# ESP32-HWE-Dev-SPI.net
KiCad netlist of a schematic drawn in Altium Designer
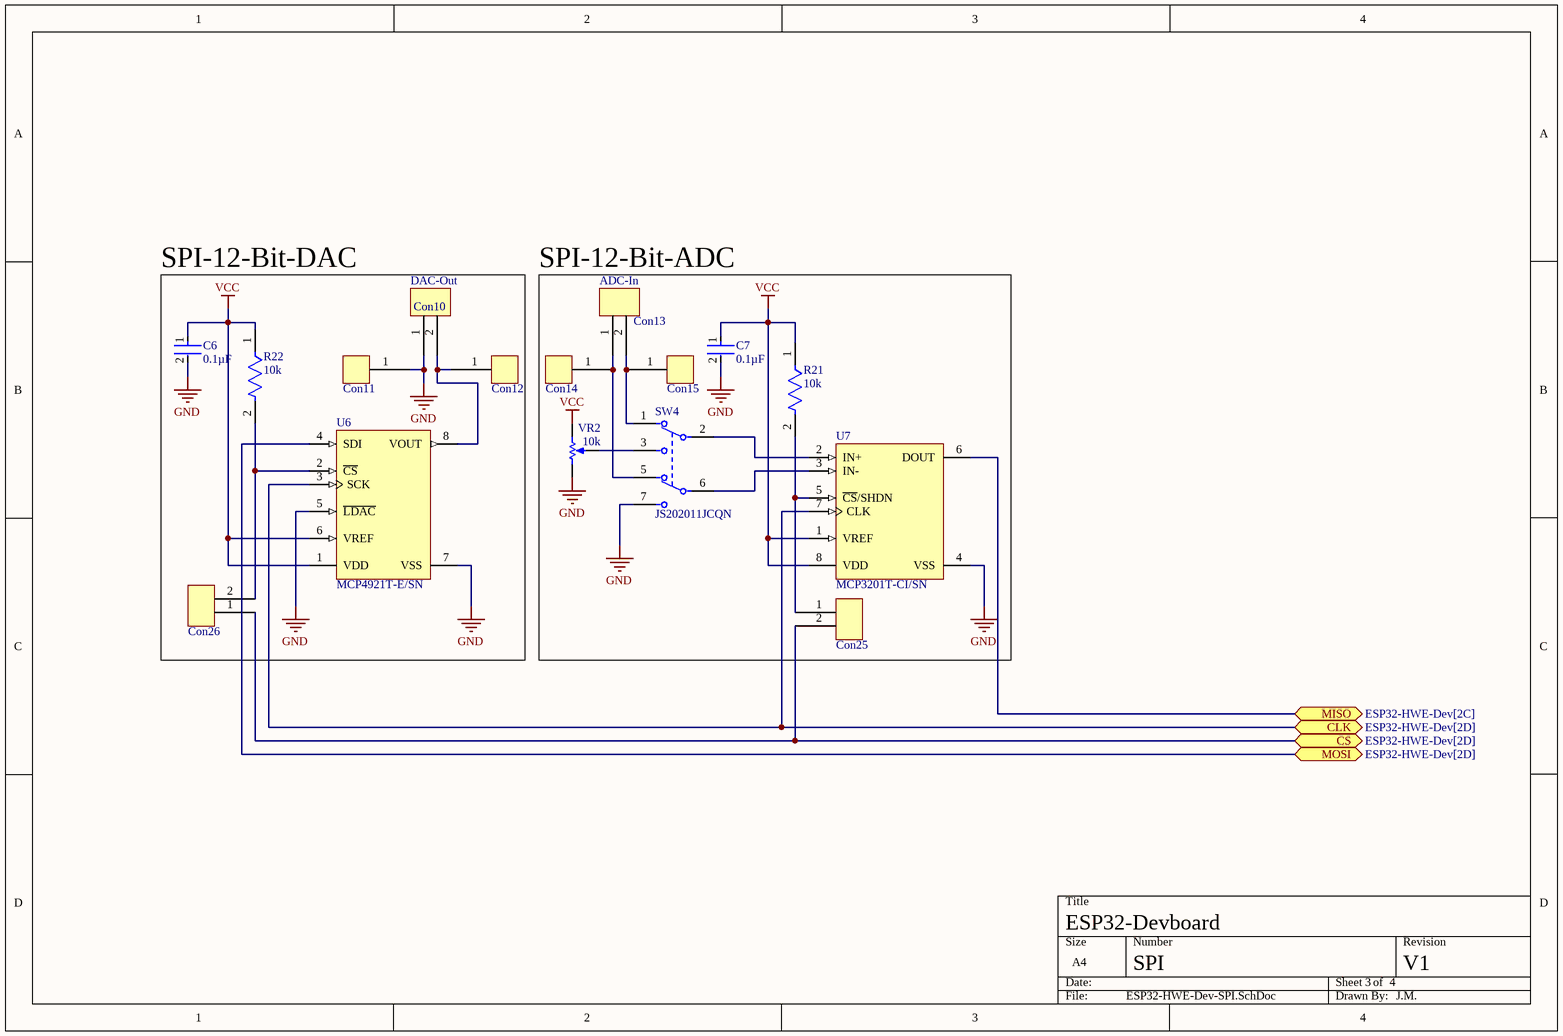
[diagram p0: ESP32-HWE-Dev-SPI.SchDoc]

(export (version "E")
  (design (tool "Eeschema 10.0.6"))
  (components
    (comp (ref "C6")
      (value "0.1µF")
      (footprint "FP-0805-L_2_01_0_2-W_1_25-IPC_C")
      (description "General Purpose Ceramic Capacitor, 0805, 100nF, 10%, X7R, 0.15, 50V")
      (fields (field (name "TOLERANCE") "10%") (field (name "VOLTAGE") "50V"))
      (libsource (lib "Altium Content Vault") (part "02cd4be3c70576c341d710602a673aa"))
    )
    (comp (ref "C7")
      (value "0.1µF")
      (footprint "FP-0805-L_2_01_0_2-W_1_25-IPC_C")
      (description "General Purpose Ceramic Capacitor, 0805, 100nF, 10%, X7R, 0.15, 50V")
      (fields (field (name "TOLERANCE") "10%") (field (name "VOLTAGE") "50V"))
      (libsource (lib "Altium Content Vault") (part "02cd4be3c70576c341d710602a673aa"))
    )
    (comp (ref "Con10")
      (value "DAC-Out")
      (footprint "Header_Female_2Pin")
      (libsource (lib "ESP32-HWE-Dev") (part "Header_Female_2Pin"))
    )
    (comp (ref "Con11")
      (value "Solder Nail RTM 1.3")
      (footprint "Solder_Nail_RTM_1.3")
      (libsource (lib "ESP32-HWE-Dev") (part "Solder_Nail_RTM_1.3"))
    )
    (comp (ref "Con12")
      (value "Solder Nail RTM 1.3")
      (footprint "Solder_Nail_RTM_1.3")
      (libsource (lib "") (part "Solder_Nail_RTM_1.3_1"))
    )
    (comp (ref "Con13")
      (value "ADC-In")
      (footprint "Header_Female_2Pin")
      (libsource (lib "ESP32-HWE-Dev") (part "Header_Female_2Pin"))
    )
    (comp (ref "Con14")
      (value "Solder Nail RTM 1.3")
      (footprint "Solder_Nail_RTM_1.3")
      (libsource (lib "ESP32-HWE-Dev") (part "Solder_Nail_RTM_1.3"))
    )
    (comp (ref "Con15")
      (value "Solder Nail RTM 1.3")
      (footprint "Solder_Nail_RTM_1.3")
      (libsource (lib "") (part "Solder_Nail_RTM_1.3_1"))
    )
    (comp (ref "Con25")
      (value "Male 2 Pin")
      (footprint "Header_Male_2Pin")
      (libsource (lib "") (part "Header_Male_2Pin_1"))
    )
    (comp (ref "Con26")
      (value "Male 2 Pin")
      (footprint "Header_Male_2Pin")
      (libsource (lib "ESP32-HWE-Dev") (part "Header_Male_2Pin"))
    )
    (comp (ref "R21")
      (value "10k")
      (footprint "FP-AC0805-MFG")
      (description "RES SMD 4.7K OHM 5% 1/8W 0805")
      (fields (field (name "MANUFACTURER") "Yageo") (field (name "TOLERANCE") "0.05"))
      (libsource (lib "Altium Content Vault") (part "1029c3af85768c4190bb7ad29bc67b5"))
    )
    (comp (ref "R22")
      (value "10k")
      (footprint "FP-AC0805-MFG")
      (description "RES SMD 4.7K OHM 5% 1/8W 0805")
      (fields (field (name "MANUFACTURER") "Yageo") (field (name "TOLERANCE") "0.05"))
      (libsource (lib "Altium Content Vault") (part "1029c3af85768c4190bb7ad29bc67b5"))
    )
    (comp (ref "SW4")
      (value "JS202011JCQN")
      (footprint "FP-JS202011JCQN-MFG")
      (description "SWITCH SLIDE DPDT 300MA 6V")
      (libsource (lib "Altium Content Vault") (part "6b3bc4f94d389b2e45f6181d1f21823"))
    )
    (comp (ref "U6")
      (value "MCP4921T-E/SN")
      (footprint "SOIC-SN8_L")
      (description "12-Bit DAC with SPI Interface, 8-Pin SOIC 150mil, Extended Temperature, Tape and Reel")
      (libsource (lib "Altium Content Vault") (part "CON-DAC-MCP4921-8"))
    )
    (comp (ref "U7")
      (value "MCP3201T-CI/SN")
      (footprint "SOIC-SN8_M")
      (libsource (lib "Altium Content Vault") (part "CON-ADC-MCP3001-8"))
    )
    (comp (ref "VR2")
      (value "10k")
      (footprint "BOUR-3362P")
      (description "Square Trimpot(R) Trimming Potentiometer, 10 KOhm, 300 V, -55 to 125 degC, 3-Pin THD, RoHS, Tube")
      (fields (field (name "TOLERANCE") "1%"))
      (libsource (lib "Altium Content Vault") (part "RES-POT-3"))
    )
  )
  (nets
    (net (code "1") (name "/CLK") (class "Default")
      (node (ref "U6") (pin "3") (pinfunction "SCK_3") (pintype "input"))
      (node (ref "U7") (pin "7") (pinfunction "CLK_7") (pintype "input"))
    )
    (net (code "2") (name "/CS") (class "Default")
      (node (ref "Con25") (pin "2") (pintype "passive"))
      (node (ref "Con26") (pin "1") (pintype "passive"))
    )
    (net (code "3") (name "/MISO") (class "Default")
      (node (ref "U7") (pin "6") (pinfunction "DOUT_6") (pintype "tri_state"))
    )
    (net (code "4") (name "/MOSI") (class "Default")
      (node (ref "U6") (pin "4") (pinfunction "SDI_4") (pintype "input"))
    )
    (net (code "5") (name "GND") (class "Default")
      (node (ref "C6") (pin "2") (pinfunction "2_2") (pintype "passive"))
      (node (ref "C7") (pin "2") (pinfunction "2_2") (pintype "passive"))
      (node (ref "Con10") (pin "1") (pintype "passive"))
      (node (ref "Con11") (pin "1") (pintype "passive"))
      (node (ref "SW4") (pin "7") (pinfunction "7_7") (pintype "passive"))
      (node (ref "U6") (pin "5") (pinfunction "~{LDAC}_5") (pintype "input"))
      (node (ref "U6") (pin "7") (pinfunction "VSS_7") (pintype "power_in"))
      (node (ref "U7") (pin "4") (pinfunction "VSS_4") (pintype "power_in"))
      (node (ref "VR2") (pin "1") (pinfunction "CCW_1") (pintype "passive"))
    )
    (net (code "6") (name "Net-(Con13-Pad1)") (class "Default")
      (node (ref "Con13") (pin "1") (pintype "passive"))
      (node (ref "Con14") (pin "1") (pintype "passive"))
      (node (ref "SW4") (pin "5") (pinfunction "5_5") (pintype "passive"))
    )
    (net (code "7") (name "Net-(Con13-Pad2)") (class "Default")
      (node (ref "Con13") (pin "2") (pintype "passive"))
      (node (ref "Con15") (pin "1") (pintype "passive"))
      (node (ref "SW4") (pin "1") (pinfunction "1_1") (pintype "passive"))
    )
    (net (code "8") (name "Net-(SW4-1_C)") (class "Default")
      (node (ref "SW4") (pin "2") (pinfunction "1_C_2") (pintype "passive"))
      (node (ref "U7") (pin "2") (pinfunction "IN+_2") (pintype "input"))
    )
    (net (code "9") (name "Net-(SW4-2_C)") (class "Default")
      (node (ref "SW4") (pin "6") (pinfunction "2_C_6") (pintype "passive"))
      (node (ref "U7") (pin "3") (pinfunction "IN-_3") (pintype "input"))
    )
    (net (code "10") (name "Net-(U6-VOUT)") (class "Default")
      (node (ref "Con10") (pin "2") (pintype "passive"))
      (node (ref "Con12") (pin "1") (pintype "passive"))
      (node (ref "U6") (pin "8") (pinfunction "VOUT_8") (pintype "output"))
    )
    (net (code "11") (name "Net-(U6-~{CS})") (class "Default")
      (node (ref "Con26") (pin "2") (pintype "passive"))
      (node (ref "R22") (pin "2") (pinfunction "2_2") (pintype "passive"))
      (node (ref "U6") (pin "2") (pinfunction "~{CS}_2") (pintype "input"))
    )
    (net (code "12") (name "Net-(U7-~{CS}{slash}SHDN)") (class "Default")
      (node (ref "Con25") (pin "1") (pintype "passive"))
      (node (ref "R21") (pin "2") (pinfunction "2_2") (pintype "passive"))
      (node (ref "U7") (pin "5") (pinfunction "~{CS}/SHDN_5") (pintype "input"))
    )
    (net (code "13") (name "Net-(VR2-S)") (class "Default")
      (node (ref "SW4") (pin "3") (pinfunction "3_3") (pintype "passive"))
      (node (ref "VR2") (pin "2") (pinfunction "S_2") (pintype "passive"))
    )
    (net (code "14") (name "VCC") (class "Default")
      (node (ref "C6") (pin "1") (pinfunction "1_1") (pintype "passive"))
      (node (ref "C7") (pin "1") (pinfunction "1_1") (pintype "passive"))
      (node (ref "R21") (pin "1") (pinfunction "1_1") (pintype "passive"))
      (node (ref "R22") (pin "1") (pinfunction "1_1") (pintype "passive"))
      (node (ref "U6") (pin "1") (pinfunction "VDD_1") (pintype "power_in"))
      (node (ref "U6") (pin "6") (pinfunction "VREF_6") (pintype "input"))
      (node (ref "U7") (pin "1") (pinfunction "VREF_1") (pintype "input"))
      (node (ref "U7") (pin "8") (pinfunction "VDD_8") (pintype "power_in"))
      (node (ref "VR2") (pin "3") (pinfunction "CW_3") (pintype "passive"))
    )
  )
)
